# I2C_OLED_DRV2605.net
KiCad netlist of a schematic drawn in Altium Designer
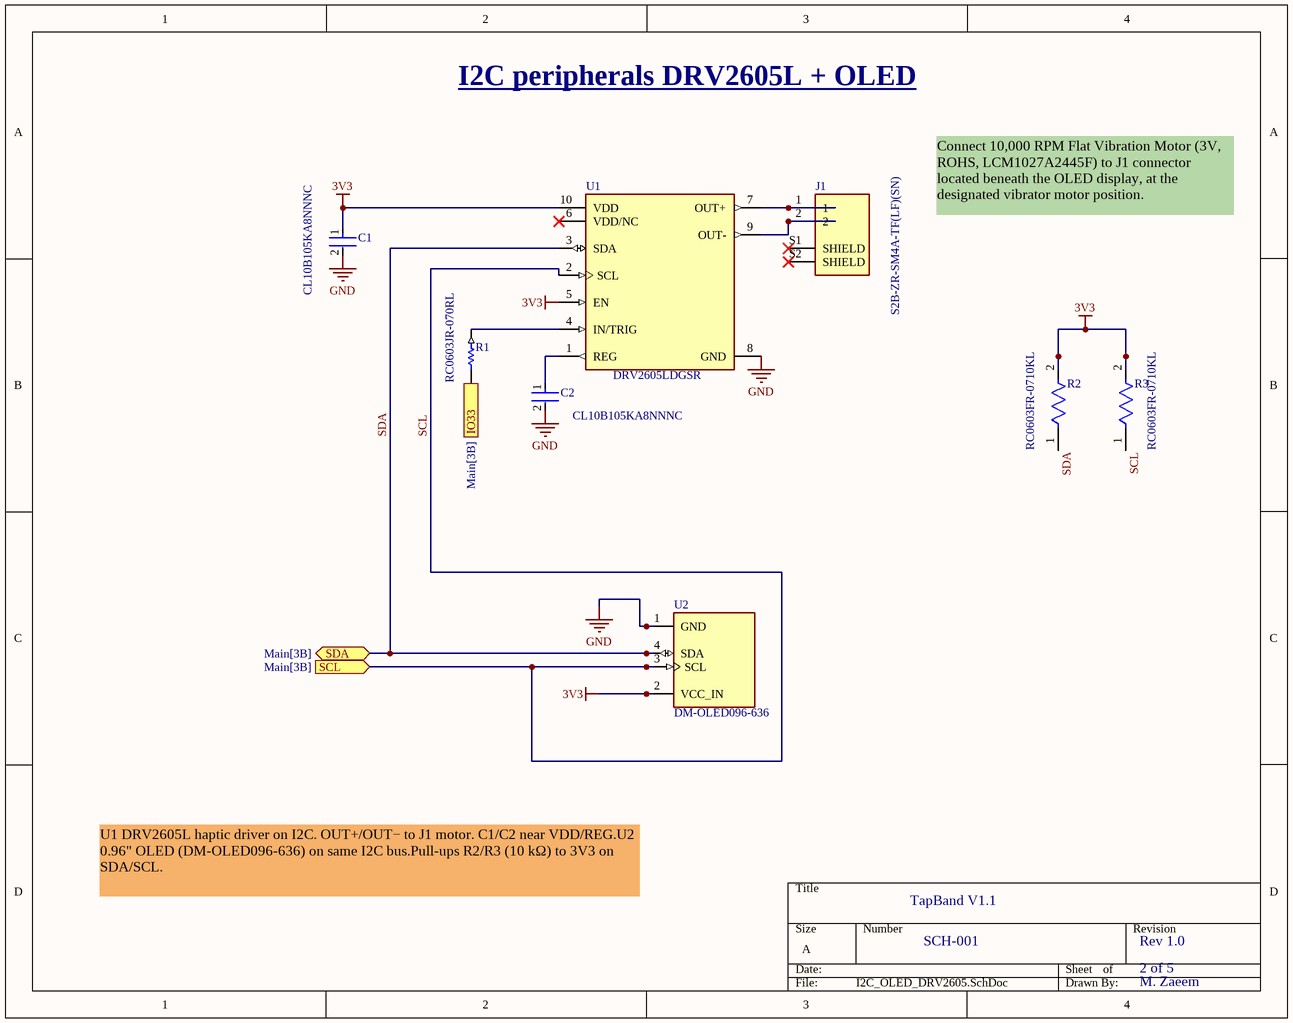
[diagram p0: I2C_OLED_DRV2605.SchDoc]

(export (version "E")
  (design (tool "Eeschema 10.0.6"))
  (components
    (comp (ref "C1")
      (value "CL10B105KA8NNNC")
      (footprint "FP-CL10-IPC_C")
      (description "CAP CER 1UF 25V X7R 0603")
      (fields (field (name "TOLERANCE") "10%") (field (name "VOLTAGE") "25V"))
      (libsource (lib "Altium Content Vault") (part "11868f565c42a9108669ba33697ecf6"))
    )
    (comp (ref "C2")
      (value "CL10B105KA8NNNC")
      (footprint "FP-CL10-IPC_C")
      (description "CAP CER 1UF 25V X7R 0603")
      (fields (field (name "TOLERANCE") "10%") (field (name "VOLTAGE") "25V"))
      (libsource (lib "Altium Content Vault") (part "11868f565c42a9108669ba33697ecf6"))
    )
    (comp (ref "J1")
      (value "S2B-ZR-SM4A-TF(LF)(SN)")
      (footprint "JST_S2B-ZR-SM4A-TF(LF)(SN)")
      (description "Connector Header Surface Mount, Right Angle 2 position 0.059 (1.50mm)")
      (fields (field (name "MF") "JST Sales") (field (name "MP") "S2B-ZR-SM4A-TF (LF)(SN)"))
      (libsource (lib "S2B-ZR-SM4A-TF(LF)(SN)") (part "S2B-ZR-SM4A-TF(LF)(SN)"))
    )
    (comp (ref "R1")
      (value "RC0603JR-070RL")
      (footprint "RESC1608X55X25ML10T15")
      (description "Chip Resistor, 0 Ohm, +/- 5%, 0.1 W, -55 to 155 degC, 0603 (1608 Metric), RoHS, Tape and Reel")
      (fields (field (name "TOLERANCE") "5%") (field (name "MANUFACTURER") "Yageo"))
      (libsource (lib "Altium Content Vault") (part "RES-2"))
    )
    (comp (ref "R2")
      (value "RC0603FR-0710KL")
      (footprint "FP-RC0603-0_55-IPC_C")
      (description "RES 10K OHM 1% 1/10W 0603")
      (fields (field (name "TOLERANCE") "1%"))
      (libsource (lib "Altium Content Vault") (part "1029c3af85768c4190bb7ad29bc67b5"))
    )
    (comp (ref "R3")
      (value "RC0603FR-0710KL")
      (footprint "FP-RC0603-0_55-IPC_C")
      (description "RES 10K OHM 1% 1/10W 0603")
      (fields (field (name "TOLERANCE") "1%"))
      (libsource (lib "Altium Content Vault") (part "1029c3af85768c4190bb7ad29bc67b5"))
    )
    (comp (ref "U1")
      (value "DRV2605LDGSR")
      (footprint "FP-DGS0010A-MFG")
      (description "IC MOTOR DRIVER 2V-5.5V 10VSSOP")
      (libsource (lib "Altium Content Vault") (part "e4ad956cc5aa131d82cbc80a2fb1c90"))
    )
    (comp (ref "U2")
      (value "DM-OLED096-636")
      (footprint "MODULE_DM-OLED096-636")
      (description "0.96â€ 128 X 64 MONOCHROME GRAPHIC OLED DISPLAY MODULE - I2C")
      (fields (field (name "MF") "Display Module"))
      (libsource (lib "DM-OLED096-636 (1)") (part "DM-OLED096-636"))
    )
  )
  (nets
    (net (code "1") (name "/IO33") (class "Default")
      (node (ref "R1") (pin "2") (pinfunction "2_2") (pintype "passive"))
    )
    (net (code "2") (name "/SCL") (class "Default")
      (node (ref "R3") (pin "1") (pinfunction "1_1") (pintype "passive"))
      (node (ref "U1") (pin "2") (pinfunction "SCL_2") (pintype "input"))
      (node (ref "U2") (pin "3") (pinfunction "SCL_3") (pintype "input"))
    )
    (net (code "3") (name "/SDA") (class "Default")
      (node (ref "R2") (pin "1") (pinfunction "1_1") (pintype "passive"))
      (node (ref "U1") (pin "3") (pinfunction "SDA_3") (pintype "bidirectional"))
      (node (ref "U2") (pin "4") (pinfunction "SDA_4") (pintype "bidirectional"))
    )
    (net (code "4") (name "3V3") (class "Default")
      (node (ref "C1") (pin "1") (pinfunction "1_1") (pintype "passive"))
      (node (ref "R2") (pin "2") (pinfunction "2_2") (pintype "passive"))
      (node (ref "R3") (pin "2") (pinfunction "2_2") (pintype "passive"))
      (node (ref "U1") (pin "10") (pinfunction "VDD_10") (pintype "power_in"))
      (node (ref "U1") (pin "5") (pinfunction "EN_5") (pintype "input"))
      (node (ref "U2") (pin "2") (pinfunction "VCC_IN_2") (pintype "power_in"))
    )
    (net (code "5") (name "GND") (class "Default")
      (node (ref "C1") (pin "2") (pinfunction "2_2") (pintype "passive"))
      (node (ref "C2") (pin "2") (pinfunction "2_2") (pintype "passive"))
      (node (ref "U1") (pin "8") (pinfunction "GND_8") (pintype "power_in"))
      (node (ref "U2") (pin "1") (pinfunction "GND_1") (pintype "power_in"))
    )
    (net (code "6") (name "Net-(U1-IN{slash}TRIG)") (class "Default")
      (node (ref "R1") (pin "1") (pinfunction "1_1") (pintype "output"))
      (node (ref "U1") (pin "4") (pinfunction "IN/TRIG_4") (pintype "input"))
    )
    (net (code "7") (name "Net-(U1-OUT+)") (class "Default")
      (node (ref "J1") (pin "1") (pinfunction "1_1") (pintype "passive"))
      (node (ref "U1") (pin "7") (pinfunction "OUT+_7") (pintype "output"))
    )
    (net (code "8") (name "Net-(U1-OUT-)") (class "Default")
      (node (ref "J1") (pin "2") (pinfunction "2_2") (pintype "passive"))
      (node (ref "U1") (pin "9") (pinfunction "OUT-_9") (pintype "output"))
    )
    (net (code "9") (name "Net-(U1-REG)") (class "Default")
      (node (ref "C2") (pin "1") (pinfunction "1_1") (pintype "passive"))
      (node (ref "U1") (pin "1") (pinfunction "REG_1") (pintype "output"))
    )
    (net (code "10") (name "unconnected-(J1-SHIELD-PadS1)") (class "Default")
      (node (ref "J1") (pin "S1") (pinfunction "SHIELD_S1") (pintype "passive+no_connect"))
    )
    (net (code "11") (name "unconnected-(J1-SHIELD-PadS2)") (class "Default")
      (node (ref "J1") (pin "S2") (pinfunction "SHIELD_S2") (pintype "passive+no_connect"))
    )
    (net (code "12") (name "unconnected-(U1-VDD{slash}NC-Pad6)") (class "Default")
      (node (ref "U1") (pin "6") (pinfunction "VDD/NC_6") (pintype "power_in+no_connect"))
    )
  )
)
